# STM32RF_MCU.net
KiCad netlist of a schematic drawn in Altium Designer
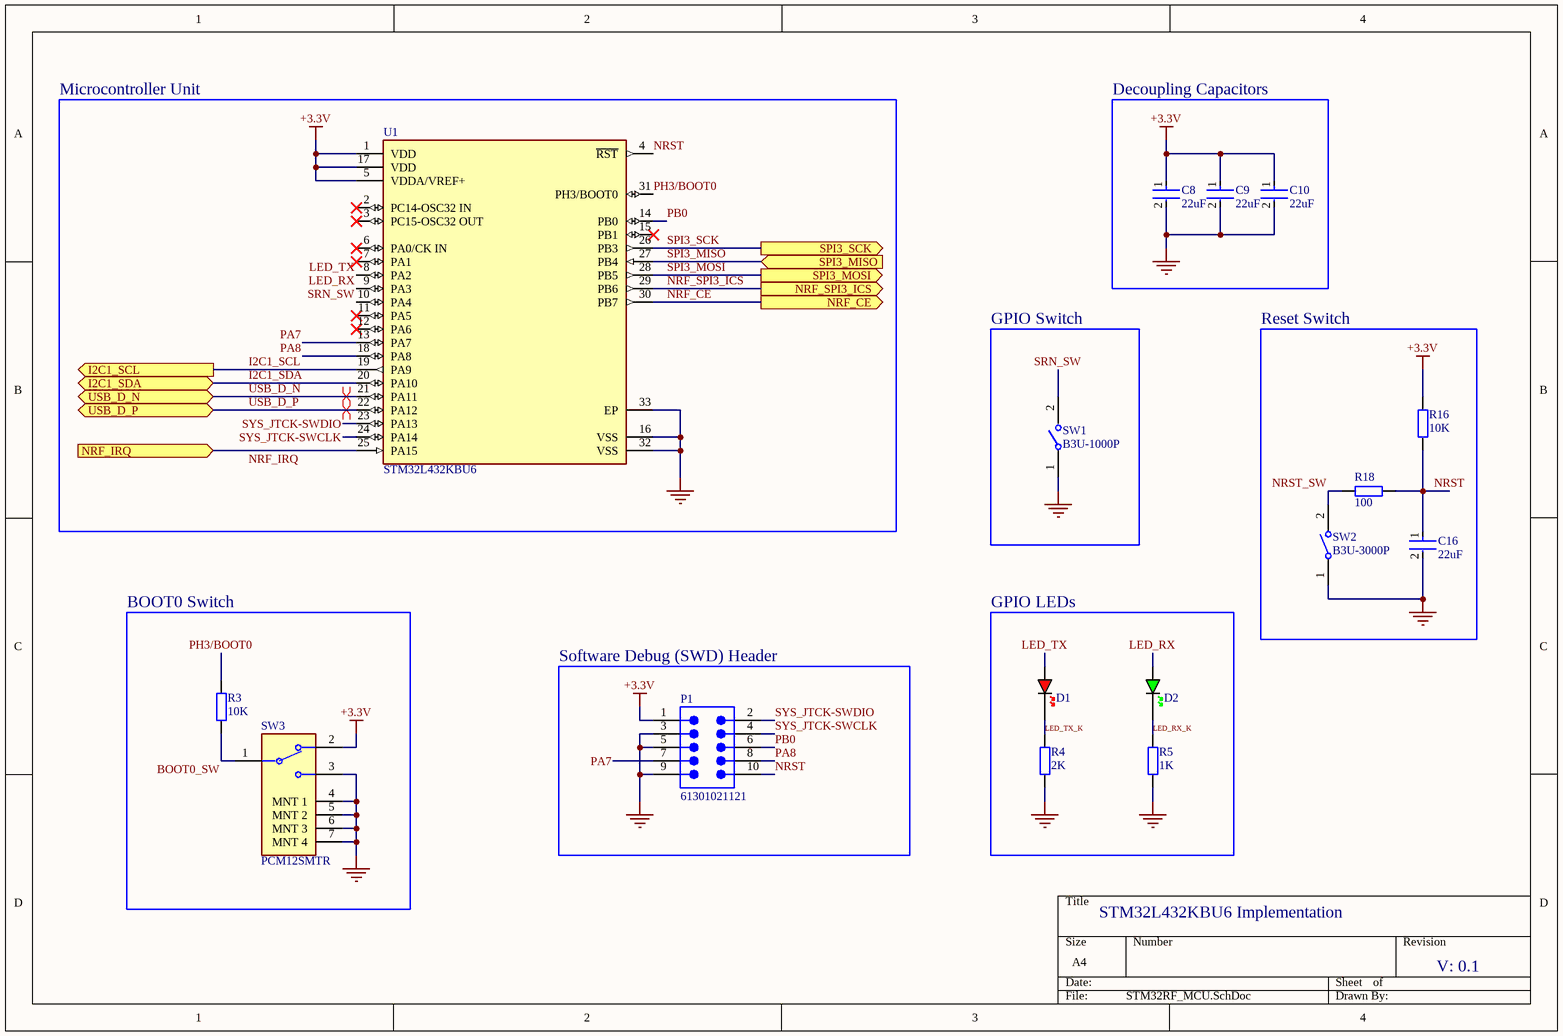
[diagram p0: STM32RF_MCU.SchDoc]

(export (version "E")
  (design (tool "Eeschema 10.0.6"))
  (components
    (comp (ref "C8")
      (value "22uF")
      (footprint "FP-GRM158-0_2-MFG")
      (description "Chip Multilayer Ceramic Capacitors for General Purpose, 0402, 22uF, X5R, 15%, 20%, 10V")
      (libsource (lib "Altium Content Vault") (part "b4654b650e69147ec39a6b967a45e02"))
    )
    (comp (ref "C9")
      (value "22uF")
      (footprint "FP-GRM158-0_2-MFG")
      (description "Chip Multilayer Ceramic Capacitors for General Purpose, 0402, 22uF, X5R, 15%, 20%, 10V")
      (libsource (lib "Altium Content Vault") (part "b4654b650e69147ec39a6b967a45e02"))
    )
    (comp (ref "C10")
      (value "22uF")
      (footprint "FP-GRM158-0_2-MFG")
      (description "Chip Multilayer Ceramic Capacitors for General Purpose, 0402, 22uF, X5R, 15%, 20%, 10V")
      (libsource (lib "Altium Content Vault") (part "b4654b650e69147ec39a6b967a45e02"))
    )
    (comp (ref "C16")
      (value "22uF")
      (footprint "FP-GRM158-0_2-MFG")
      (description "Chip Multilayer Ceramic Capacitors for General Purpose, 0402, 22uF, X5R, 15%, 20%, 10V")
      (libsource (lib "Altium Content Vault") (part "b4654b650e69147ec39a6b967a45e02"))
    )
    (comp (ref "D1")
      (value "RED")
      (footprint "LED_0402_RED")
      (description "LED 0402 RED SMD")
      (libsource (lib "Schematic-Lib-PhilsLab") (part "LED_0402_RED"))
    )
    (comp (ref "D2")
      (value "GREEN")
      (footprint "LED_0402_GREEN")
      (description "LED 0402 GREEN SMD")
      (libsource (lib "Schematic-Lib-PhilsLab") (part "LED_0402_GREEN"))
    )
    (comp (ref "P1")
      (value "61301021121")
      (footprint "61301021121")
      (description "THT Vertical Pin Header WR-PHD, Pitch 2.54 mm, Dual Row, 10 pins")
      (libsource (lib "Altium Content Vault") (part "Header_Male_2R_10P"))
    )
    (comp (ref "R3")
      (value "10K")
      (footprint "RES_0402")
      (description "Resistor SMD 0402")
      (libsource (lib "Schematic-Lib-PhilsLab") (part "RES_0402"))
    )
    (comp (ref "R4")
      (value "2K")
      (footprint "RES_0402")
      (description "Resistor SMD 0402")
      (libsource (lib "Schematic-Lib-PhilsLab") (part "RES_0402"))
    )
    (comp (ref "R5")
      (value "1K")
      (footprint "RES_0402")
      (description "Resistor SMD 0402")
      (libsource (lib "Schematic-Lib-PhilsLab") (part "RES_0402"))
    )
    (comp (ref "R16")
      (value "10K")
      (footprint "RES_0402")
      (description "Resistor SMD 0402")
      (libsource (lib "Schematic-Lib-PhilsLab") (part "RES_0402"))
    )
    (comp (ref "R18")
      (value "100")
      (footprint "RES_0402")
      (description "Resistor SMD 0402")
      (libsource (lib "Schematic-Lib-PhilsLab") (part "RES_0402"))
    )
    (comp (ref "SW1")
      (value "B3U-1000P")
      (footprint "FP-B3U-1000P-MFG")
      (description "SWITCH TACTILE SPST-NO 0.05A 12V")
      (libsource (lib "Altium Content Vault") (part "ae622034201233ca1abcedc05908f33"))
    )
    (comp (ref "SW2")
      (value "B3U-3000P")
      (footprint "OMRON-B3U-3000P_V")
      (description "Ultra-Small Tactile Switch, 1 to 50 mA, 3 to 12 V, -25 to 70 degC, 2-Pin SMD, RoHS, Tape and Reel")
      (fields (field (name "TOLERANCE") "20%"))
      (libsource (lib "Altium Content Vault") (part "SW-SPST-2_B"))
    )
    (comp (ref "SW3")
      (value "PCM12SMTR")
      (footprint "FP-PCM12SMTR-MFG")
      (description "SWITCH SLIDE SPDT 300MA 6V")
      (libsource (lib "Altium Content Vault") (part "1a3f67d7e2b5469b171eeab59ffb4d2"))
    )
    (comp (ref "U1")
      (value "STM32L432KBU6")
      (footprint "FP-UFQFPN32-A0B8-MFG")
      (description "IC MCU 32BIT 128KB FLASH 32QFPN")
      (fields
        (field (name "MANUFACTURER") "STMicroelectronics")
        (field (name "OCTOPART") "https://octopart.com/stm32l432kbu6-stmicroelectronics-74568735")
      )
      (libsource (lib "Altium Content Vault") (part "2d0dd149e1b71adbded20be99a489b5"))
    )
  )
  (nets
    (net (code "1") (name "+3.3V") (class "Default")
      (node (ref "C10") (pin "1") (pinfunction "1_1") (pintype "passive"))
      (node (ref "C8") (pin "1") (pinfunction "1_1") (pintype "passive"))
      (node (ref "C9") (pin "1") (pinfunction "1_1") (pintype "passive"))
      (node (ref "P1") (pin "1") (pinfunction "1_1") (pintype "passive"))
      (node (ref "R16") (pin "2") (pinfunction "2_2") (pintype "passive"))
      (node (ref "SW3") (pin "2") (pinfunction "2_2") (pintype "passive"))
      (node (ref "U1") (pin "1") (pinfunction "VDD_1") (pintype "power_in"))
      (node (ref "U1") (pin "17") (pinfunction "VDD_17") (pintype "power_in"))
      (node (ref "U1") (pin "5") (pinfunction "VDDA/VREF+_5") (pintype "power_in"))
    )
    (net (code "2") (name "/BOOT0_SW") (class "Default")
      (node (ref "R3") (pin "1") (pinfunction "1_1") (pintype "passive"))
      (node (ref "SW3") (pin "1") (pinfunction "1_1") (pintype "passive"))
    )
    (net (code "3") (name "/I2C1_SCL") (class "Default")
      (node (ref "U1") (pin "19") (pinfunction "PA9_19") (pintype "output"))
    )
    (net (code "4") (name "/I2C1_SDA") (class "Default")
      (node (ref "U1") (pin "20") (pinfunction "PA10_20") (pintype "bidirectional"))
    )
    (net (code "5") (name "/LED_RX") (class "Default")
      (node (ref "D2") (pin "A") (pinfunction "A_A") (pintype "passive"))
      (node (ref "U1") (pin "9") (pinfunction "PA3_9") (pintype "bidirectional"))
    )
    (net (code "6") (name "/LED_RX_K") (class "Default")
      (node (ref "D2") (pin "K") (pinfunction "K_K") (pintype "passive"))
      (node (ref "R5") (pin "2") (pinfunction "2_2") (pintype "passive"))
    )
    (net (code "7") (name "/LED_TX") (class "Default")
      (node (ref "D1") (pin "A") (pinfunction "A_A") (pintype "passive"))
      (node (ref "U1") (pin "8") (pinfunction "PA2_8") (pintype "bidirectional"))
    )
    (net (code "8") (name "/LED_TX_K") (class "Default")
      (node (ref "D1") (pin "K") (pinfunction "K_K") (pintype "passive"))
      (node (ref "R4") (pin "2") (pinfunction "2_2") (pintype "passive"))
    )
    (net (code "9") (name "/NRF_CE") (class "Default")
      (node (ref "U1") (pin "30") (pinfunction "PB7_30") (pintype "output"))
    )
    (net (code "10") (name "/NRF_IRQ") (class "Default")
      (node (ref "U1") (pin "25") (pinfunction "PA15_25") (pintype "input"))
    )
    (net (code "11") (name "/NRF_SPI3_ICS") (class "Default")
      (node (ref "U1") (pin "29") (pinfunction "PB6_29") (pintype "output"))
    )
    (net (code "12") (name "/NRST") (class "Default")
      (node (ref "C16") (pin "1") (pinfunction "1_1") (pintype "passive"))
      (node (ref "P1") (pin "10") (pinfunction "10_10") (pintype "passive"))
      (node (ref "R16") (pin "1") (pinfunction "1_1") (pintype "passive"))
      (node (ref "R18") (pin "1") (pinfunction "1_1") (pintype "passive"))
      (node (ref "U1") (pin "4") (pinfunction "~{RST}_4") (pintype "output"))
    )
    (net (code "13") (name "/NRST_SW") (class "Default")
      (node (ref "R18") (pin "2") (pinfunction "2_2") (pintype "passive"))
      (node (ref "SW2") (pin "2") (pinfunction "2_2") (pintype "passive"))
    )
    (net (code "14") (name "/PA7") (class "Default")
      (node (ref "P1") (pin "7") (pinfunction "7_7") (pintype "passive"))
      (node (ref "U1") (pin "13") (pinfunction "PA7_13") (pintype "bidirectional"))
    )
    (net (code "15") (name "/PA8") (class "Default")
      (node (ref "P1") (pin "8") (pinfunction "8_8") (pintype "passive"))
      (node (ref "U1") (pin "18") (pinfunction "PA8_18") (pintype "bidirectional"))
    )
    (net (code "16") (name "/PB0") (class "Default")
      (node (ref "P1") (pin "6") (pinfunction "6_6") (pintype "passive"))
      (node (ref "U1") (pin "14") (pinfunction "PB0_14") (pintype "bidirectional"))
    )
    (net (code "17") (name "/PH3{slash}BOOT0") (class "Default")
      (node (ref "R3") (pin "2") (pinfunction "2_2") (pintype "passive"))
      (node (ref "U1") (pin "31") (pinfunction "PH3/BOOT0_31") (pintype "bidirectional"))
    )
    (net (code "18") (name "/SPI3_MISO") (class "Default")
      (node (ref "U1") (pin "27") (pinfunction "PB4_27") (pintype "input"))
    )
    (net (code "19") (name "/SPI3_MOSI") (class "Default")
      (node (ref "U1") (pin "28") (pinfunction "PB5_28") (pintype "output"))
    )
    (net (code "20") (name "/SPI3_SCK") (class "Default")
      (node (ref "U1") (pin "26") (pinfunction "PB3_26") (pintype "output"))
    )
    (net (code "21") (name "/SRN_SW") (class "Default")
      (node (ref "SW1") (pin "2") (pinfunction "2_2") (pintype "passive"))
      (node (ref "U1") (pin "10") (pinfunction "PA4_10") (pintype "bidirectional"))
    )
    (net (code "22") (name "/SYS_JTCK-SWCLK") (class "Default")
      (node (ref "P1") (pin "4") (pinfunction "4_4") (pintype "passive"))
      (node (ref "U1") (pin "24") (pinfunction "PA14_24") (pintype "bidirectional"))
    )
    (net (code "23") (name "/SYS_JTCK-SWDIO") (class "Default")
      (node (ref "P1") (pin "2") (pinfunction "2_2") (pintype "passive"))
      (node (ref "U1") (pin "23") (pinfunction "PA13_23") (pintype "bidirectional"))
    )
    (net (code "24") (name "/USB_D_N") (class "Default")
      (node (ref "U1") (pin "21") (pinfunction "PA11_21") (pintype "bidirectional"))
    )
    (net (code "25") (name "/USB_D_P") (class "Default")
      (node (ref "U1") (pin "22") (pinfunction "PA12_22") (pintype "bidirectional"))
    )
    (net (code "26") (name "GND") (class "Default")
      (node (ref "C10") (pin "2") (pinfunction "2_2") (pintype "passive"))
      (node (ref "C16") (pin "2") (pinfunction "2_2") (pintype "passive"))
      (node (ref "C8") (pin "2") (pinfunction "2_2") (pintype "passive"))
      (node (ref "C9") (pin "2") (pinfunction "2_2") (pintype "passive"))
      (node (ref "P1") (pin "3") (pinfunction "3_3") (pintype "passive"))
      (node (ref "P1") (pin "5") (pinfunction "5_5") (pintype "passive"))
      (node (ref "P1") (pin "9") (pinfunction "9_9") (pintype "passive"))
      (node (ref "R4") (pin "1") (pinfunction "1_1") (pintype "passive"))
      (node (ref "R5") (pin "1") (pinfunction "1_1") (pintype "passive"))
      (node (ref "SW1") (pin "1") (pinfunction "1_1") (pintype "passive"))
      (node (ref "SW2") (pin "1") (pinfunction "1_1") (pintype "passive"))
      (node (ref "SW3") (pin "3") (pinfunction "3_3") (pintype "passive"))
      (node (ref "SW3") (pin "4") (pinfunction "MNT_1_4") (pintype "passive"))
      (node (ref "SW3") (pin "5") (pinfunction "MNT_2_5") (pintype "passive"))
      (node (ref "SW3") (pin "6") (pinfunction "MNT_3_6") (pintype "passive"))
      (node (ref "SW3") (pin "7") (pinfunction "MNT_4_7") (pintype "passive"))
      (node (ref "U1") (pin "16") (pinfunction "VSS_16") (pintype "power_in"))
      (node (ref "U1") (pin "32") (pinfunction "VSS_32") (pintype "power_in"))
      (node (ref "U1") (pin "33") (pinfunction "EP_33") (pintype "power_in"))
    )
    (net (code "27") (name "unconnected-(U1-PA0{slash}CK_IN-Pad6)") (class "Default")
      (node (ref "U1") (pin "6") (pinfunction "PA0/CK_IN_6") (pintype "bidirectional+no_connect"))
    )
    (net (code "28") (name "unconnected-(U1-PA1-Pad7)") (class "Default")
      (node (ref "U1") (pin "7") (pinfunction "PA1_7") (pintype "bidirectional+no_connect"))
    )
    (net (code "29") (name "unconnected-(U1-PA5-Pad11)") (class "Default")
      (node (ref "U1") (pin "11") (pinfunction "PA5_11") (pintype "bidirectional+no_connect"))
    )
    (net (code "30") (name "unconnected-(U1-PA6-Pad12)") (class "Default")
      (node (ref "U1") (pin "12") (pinfunction "PA6_12") (pintype "bidirectional+no_connect"))
    )
    (net (code "31") (name "unconnected-(U1-PB1-Pad15)") (class "Default")
      (node (ref "U1") (pin "15") (pinfunction "PB1_15") (pintype "bidirectional+no_connect"))
    )
    (net (code "32") (name "unconnected-(U1-PC14-OSC32_IN-Pad2)") (class "Default")
      (node (ref "U1") (pin "2") (pinfunction "PC14-OSC32_IN_2") (pintype "bidirectional+no_connect"))
    )
    (net (code "33") (name "unconnected-(U1-PC15-OSC32_OUT-Pad3)") (class "Default")
      (node (ref "U1") (pin "3") (pinfunction "PC15-OSC32_OUT_3") (pintype "bidirectional+no_connect"))
    )
  )
)
